# WIFI.net
KiCad netlist of a schematic drawn in Altium Designer
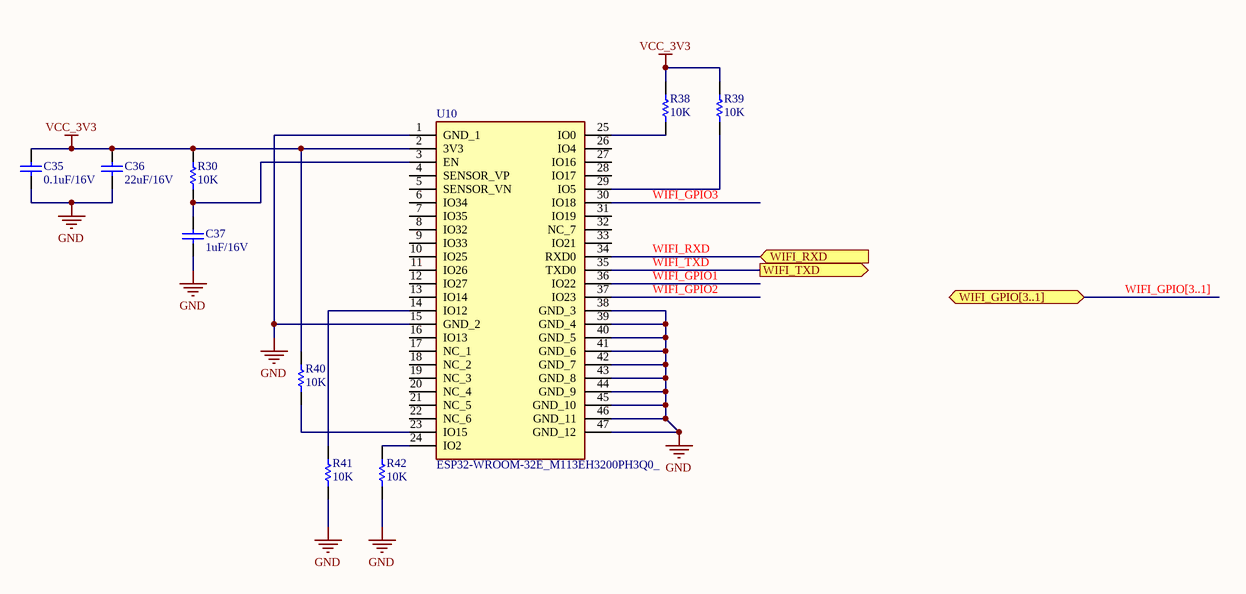
[diagram p0: WIFI.SchDoc]

(export (version "E")
  (design (tool "Eeschema 10.0.6"))
  (components
    (comp (ref "C35")
      (value "0.1uF/16V")
      (footprint "RAD-0.3")
      (description "Capacitor")
      (fields (field (name "PUBLISHER") "Altium Limited"))
      (libsource (lib "Miscellaneous Devices") (part "Cap"))
    )
    (comp (ref "C36")
      (value "22uF/16V")
      (footprint "RAD-0.3")
      (description "Capacitor")
      (fields (field (name "PUBLISHER") "Altium Limited"))
      (libsource (lib "Miscellaneous Devices") (part "Cap"))
    )
    (comp (ref "C37")
      (value "1uF/16V")
      (footprint "RAD-0.3")
      (description "Capacitor")
      (fields (field (name "PUBLISHER") "Altium Limited"))
      (libsource (lib "Miscellaneous Devices") (part "Cap"))
    )
    (comp (ref "R30")
      (value "10K")
      (footprint "AXIAL-0.3")
      (description "Resistor")
      (fields (field (name "PUBLISHER") "Altium Limited"))
      (libsource (lib "Miscellaneous Devices") (part "Res1"))
    )
    (comp (ref "R38")
      (value "10K")
      (footprint "AXIAL-0.3")
      (description "Resistor")
      (fields (field (name "PUBLISHER") "Altium Limited"))
      (libsource (lib "Miscellaneous Devices") (part "Res1"))
    )
    (comp (ref "R39")
      (value "10K")
      (footprint "AXIAL-0.3")
      (description "Resistor")
      (fields (field (name "PUBLISHER") "Altium Limited"))
      (libsource (lib "Miscellaneous Devices") (part "Res1"))
    )
    (comp (ref "R40")
      (value "10K")
      (footprint "AXIAL-0.3")
      (description "Resistor")
      (fields (field (name "PUBLISHER") "Altium Limited"))
      (libsource (lib "Miscellaneous Devices") (part "Res1"))
    )
    (comp (ref "R41")
      (value "10K")
      (footprint "AXIAL-0.3")
      (description "Resistor")
      (fields (field (name "PUBLISHER") "Altium Limited"))
      (libsource (lib "Miscellaneous Devices") (part "Res1"))
    )
    (comp (ref "R42")
      (value "10K")
      (footprint "AXIAL-0.3")
      (description "Resistor")
      (fields (field (name "PUBLISHER") "Altium Limited"))
      (libsource (lib "Miscellaneous Devices") (part "Res1"))
    )
    (comp (ref "U10")
      (value "ESP32-WROOM-32E_M113EH3200PH3Q0_")
      (footprint "SamacSys:ESP32WROOM32EM113EH3200PH3Q0")
      (description "Integrated Circuit")
      (fields
        (field (name "MANUFACTURER_PART_NUMBER") "ESP32-WROOM-32E(M113EH3200PH3Q0)")
        (field (name "MOUSER PART NUMBER") "356-ESP32WRM32E132PH")
      )
      (libsource (lib "*") (part "ESP32-WROOM-32E_M113EH3200PH3Q0_"))
    )
  )
  (nets
    (net (code "1") (name "/WIFI_GPIO1") (class "Default")
      (node (ref "U10") (pin "36") (pinfunction "IO22_36") (pintype "passive"))
    )
    (net (code "2") (name "/WIFI_GPIO2") (class "Default")
      (node (ref "U10") (pin "37") (pinfunction "IO23_37") (pintype "passive"))
    )
    (net (code "3") (name "/WIFI_GPIO3") (class "Default")
      (node (ref "U10") (pin "30") (pinfunction "IO18_30") (pintype "passive"))
    )
    (net (code "5") (name "/WIFI_RXD") (class "Default")
      (node (ref "U10") (pin "34") (pinfunction "RXD0_34") (pintype "passive"))
    )
    (net (code "6") (name "/WIFI_TXD") (class "Default")
      (node (ref "U10") (pin "35") (pinfunction "TXD0_35") (pintype "passive"))
    )
    (net (code "7") (name "GND") (class "Default")
      (node (ref "C35") (pin "2") (pinfunction "2_2") (pintype "passive"))
      (node (ref "C36") (pin "2") (pinfunction "2_2") (pintype "passive"))
      (node (ref "C37") (pin "2") (pinfunction "2_2") (pintype "passive"))
      (node (ref "R41") (pin "2") (pinfunction "2_2") (pintype "passive"))
      (node (ref "R42") (pin "2") (pinfunction "2_2") (pintype "passive"))
      (node (ref "U10") (pin "1") (pinfunction "GND_1_1") (pintype "passive"))
      (node (ref "U10") (pin "15") (pinfunction "GND_2_15") (pintype "passive"))
      (node (ref "U10") (pin "38") (pinfunction "GND_3_38") (pintype "passive"))
      (node (ref "U10") (pin "39") (pinfunction "GND_4_39") (pintype "passive"))
      (node (ref "U10") (pin "40") (pinfunction "GND_5_40") (pintype "passive"))
      (node (ref "U10") (pin "41") (pinfunction "GND_6_41") (pintype "passive"))
      (node (ref "U10") (pin "42") (pinfunction "GND_7_42") (pintype "passive"))
      (node (ref "U10") (pin "43") (pinfunction "GND_8_43") (pintype "passive"))
      (node (ref "U10") (pin "44") (pinfunction "GND_9_44") (pintype "passive"))
      (node (ref "U10") (pin "45") (pinfunction "GND_10_45") (pintype "passive"))
      (node (ref "U10") (pin "46") (pinfunction "GND_11_46") (pintype "passive"))
      (node (ref "U10") (pin "47") (pinfunction "GND_12_47") (pintype "passive"))
    )
    (net (code "8") (name "Net-(U10-EN)") (class "Default")
      (node (ref "C37") (pin "1") (pinfunction "1_1") (pintype "passive"))
      (node (ref "R30") (pin "2") (pinfunction "2_2") (pintype "passive"))
      (node (ref "U10") (pin "3") (pinfunction "EN_3") (pintype "passive"))
    )
    (net (code "9") (name "Net-(U10-IO0)") (class "Default")
      (node (ref "R38") (pin "2") (pinfunction "2_2") (pintype "passive"))
      (node (ref "U10") (pin "25") (pinfunction "IO0_25") (pintype "passive"))
    )
    (net (code "10") (name "Net-(U10-IO2)") (class "Default")
      (node (ref "R42") (pin "1") (pinfunction "1_1") (pintype "passive"))
      (node (ref "U10") (pin "24") (pinfunction "IO2_24") (pintype "passive"))
    )
    (net (code "11") (name "Net-(U10-IO5)") (class "Default")
      (node (ref "R39") (pin "2") (pinfunction "2_2") (pintype "passive"))
      (node (ref "U10") (pin "29") (pinfunction "IO5_29") (pintype "passive"))
    )
    (net (code "12") (name "Net-(U10-IO12)") (class "Default")
      (node (ref "R41") (pin "1") (pinfunction "1_1") (pintype "passive"))
      (node (ref "U10") (pin "14") (pinfunction "IO12_14") (pintype "passive"))
    )
    (net (code "13") (name "Net-(U10-IO15)") (class "Default")
      (node (ref "R40") (pin "2") (pinfunction "2_2") (pintype "passive"))
      (node (ref "U10") (pin "23") (pinfunction "IO15_23") (pintype "passive"))
    )
    (net (code "14") (name "VCC_3V3") (class "Default")
      (node (ref "C35") (pin "1") (pinfunction "1_1") (pintype "passive"))
      (node (ref "C36") (pin "1") (pinfunction "1_1") (pintype "passive"))
      (node (ref "R30") (pin "1") (pinfunction "1_1") (pintype "passive"))
      (node (ref "R38") (pin "1") (pinfunction "1_1") (pintype "passive"))
      (node (ref "R39") (pin "1") (pinfunction "1_1") (pintype "passive"))
      (node (ref "R40") (pin "1") (pinfunction "1_1") (pintype "passive"))
      (node (ref "U10") (pin "2") (pinfunction "3V3_2") (pintype "passive"))
    )
    (net (code "15") (name "unconnected-(U10-IO4-Pad26)") (class "Default")
      (node (ref "U10") (pin "26") (pinfunction "IO4_26") (pintype "passive"))
    )
    (net (code "16") (name "unconnected-(U10-IO13-Pad16)") (class "Default")
      (node (ref "U10") (pin "16") (pinfunction "IO13_16") (pintype "passive"))
    )
    (net (code "17") (name "unconnected-(U10-IO14-Pad13)") (class "Default")
      (node (ref "U10") (pin "13") (pinfunction "IO14_13") (pintype "passive"))
    )
    (net (code "18") (name "unconnected-(U10-IO16-Pad27)") (class "Default")
      (node (ref "U10") (pin "27") (pinfunction "IO16_27") (pintype "passive"))
    )
    (net (code "19") (name "unconnected-(U10-IO17-Pad28)") (class "Default")
      (node (ref "U10") (pin "28") (pinfunction "IO17_28") (pintype "passive"))
    )
    (net (code "20") (name "unconnected-(U10-IO19-Pad31)") (class "Default")
      (node (ref "U10") (pin "31") (pinfunction "IO19_31") (pintype "passive"))
    )
    (net (code "21") (name "unconnected-(U10-IO21-Pad33)") (class "Default")
      (node (ref "U10") (pin "33") (pinfunction "IO21_33") (pintype "passive"))
    )
    (net (code "22") (name "unconnected-(U10-IO25-Pad10)") (class "Default")
      (node (ref "U10") (pin "10") (pinfunction "IO25_10") (pintype "passive"))
    )
    (net (code "23") (name "unconnected-(U10-IO26-Pad11)") (class "Default")
      (node (ref "U10") (pin "11") (pinfunction "IO26_11") (pintype "passive"))
    )
    (net (code "24") (name "unconnected-(U10-IO27-Pad12)") (class "Default")
      (node (ref "U10") (pin "12") (pinfunction "IO27_12") (pintype "passive"))
    )
    (net (code "25") (name "unconnected-(U10-IO32-Pad8)") (class "Default")
      (node (ref "U10") (pin "8") (pinfunction "IO32_8") (pintype "passive"))
    )
    (net (code "26") (name "unconnected-(U10-IO33-Pad9)") (class "Default")
      (node (ref "U10") (pin "9") (pinfunction "IO33_9") (pintype "passive"))
    )
    (net (code "27") (name "unconnected-(U10-IO34-Pad6)") (class "Default")
      (node (ref "U10") (pin "6") (pinfunction "IO34_6") (pintype "passive"))
    )
    (net (code "28") (name "unconnected-(U10-IO35-Pad7)") (class "Default")
      (node (ref "U10") (pin "7") (pinfunction "IO35_7") (pintype "passive"))
    )
    (net (code "29") (name "unconnected-(U10-NC_1-Pad17)") (class "Default")
      (node (ref "U10") (pin "17") (pinfunction "NC_1_17") (pintype "passive"))
    )
    (net (code "30") (name "unconnected-(U10-NC_2-Pad18)") (class "Default")
      (node (ref "U10") (pin "18") (pinfunction "NC_2_18") (pintype "passive"))
    )
    (net (code "31") (name "unconnected-(U10-NC_3-Pad19)") (class "Default")
      (node (ref "U10") (pin "19") (pinfunction "NC_3_19") (pintype "passive"))
    )
    (net (code "32") (name "unconnected-(U10-NC_4-Pad20)") (class "Default")
      (node (ref "U10") (pin "20") (pinfunction "NC_4_20") (pintype "passive"))
    )
    (net (code "33") (name "unconnected-(U10-NC_5-Pad21)") (class "Default")
      (node (ref "U10") (pin "21") (pinfunction "NC_5_21") (pintype "passive"))
    )
    (net (code "34") (name "unconnected-(U10-NC_6-Pad22)") (class "Default")
      (node (ref "U10") (pin "22") (pinfunction "NC_6_22") (pintype "passive"))
    )
    (net (code "35") (name "unconnected-(U10-NC_7-Pad32)") (class "Default")
      (node (ref "U10") (pin "32") (pinfunction "NC_7_32") (pintype "passive"))
    )
    (net (code "36") (name "unconnected-(U10-SENSOR_VN-Pad5)") (class "Default")
      (node (ref "U10") (pin "5") (pinfunction "SENSOR_VN_5") (pintype "passive"))
    )
    (net (code "37") (name "unconnected-(U10-SENSOR_VP-Pad4)") (class "Default")
      (node (ref "U10") (pin "4") (pinfunction "SENSOR_VP_4") (pintype "passive"))
    )
  )
)
